# eagle-TSL230RD.net
KiCad netlist of a schematic drawn in EAGLE
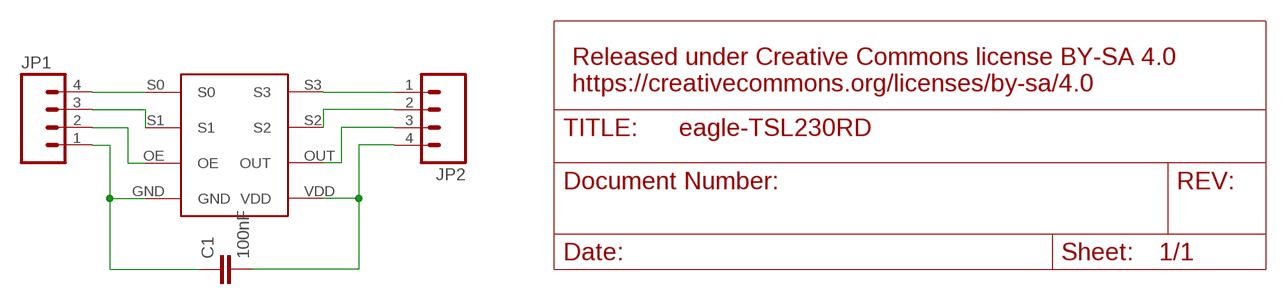
[diagram p0: schematic, sheet 1]

(export (version "E")
  (design (tool "Eeschema 10.0.6"))
  (components
    (comp (ref "C1")
      (value "100nF")
      (footprint "eagle-import:0805")
      (libsource (lib "eagle-import") (part "CAP0805"))
    )
    (comp (ref "JP1")
      (value "M04PTH")
      (footprint "eagle-import:1X04")
      (libsource (lib "eagle-import") (part "M04PTH"))
    )
    (comp (ref "JP2")
      (value "M04PTH")
      (footprint "eagle-import:1X04")
      (libsource (lib "eagle-import") (part "M04PTH"))
    )
    (comp (ref "U$1")
      (value "TSL230RDSMD")
      (footprint "eagle-import:TSL230RD")
      (libsource (lib "eagle-import") (part "TSL230RDSMD"))
    )
  )
  (nets
    (net (code "1") (name "Net-(C1-Pad1)") (class "Default")
      (node (ref "C1") (pin "1") (pinfunction "1_1") (pintype "passive"))
      (node (ref "JP1") (pin "1") (pinfunction "1_1") (pintype "passive"))
      (node (ref "U$1") (pin "GND") (pinfunction "GND_GND") (pintype "bidirectional"))
    )
    (net (code "2") (name "Net-(C1-Pad2)") (class "Default")
      (node (ref "C1") (pin "2") (pinfunction "2_2") (pintype "passive"))
      (node (ref "JP2") (pin "4") (pinfunction "4_4") (pintype "passive"))
      (node (ref "U$1") (pin "VDD") (pinfunction "VDD_VDD") (pintype "bidirectional"))
    )
    (net (code "3") (name "Net-(JP1-Pad2)") (class "Default")
      (node (ref "JP1") (pin "2") (pinfunction "2_2") (pintype "passive"))
      (node (ref "U$1") (pin "OE") (pinfunction "OE_OE") (pintype "bidirectional"))
    )
    (net (code "4") (name "Net-(JP1-Pad3)") (class "Default")
      (node (ref "JP1") (pin "3") (pinfunction "3_3") (pintype "passive"))
      (node (ref "U$1") (pin "S1") (pinfunction "S1_S1") (pintype "bidirectional"))
    )
    (net (code "5") (name "Net-(JP1-Pad4)") (class "Default")
      (node (ref "JP1") (pin "4") (pinfunction "4_4") (pintype "passive"))
      (node (ref "U$1") (pin "S0") (pinfunction "S0_S0") (pintype "bidirectional"))
    )
    (net (code "6") (name "Net-(JP2-Pad1)") (class "Default")
      (node (ref "JP2") (pin "1") (pinfunction "1_1") (pintype "passive"))
      (node (ref "U$1") (pin "S3") (pinfunction "S3_S3") (pintype "bidirectional"))
    )
    (net (code "7") (name "Net-(JP2-Pad2)") (class "Default")
      (node (ref "JP2") (pin "2") (pinfunction "2_2") (pintype "passive"))
      (node (ref "U$1") (pin "S2") (pinfunction "S2_S2") (pintype "bidirectional"))
    )
    (net (code "8") (name "Net-(JP2-Pad3)") (class "Default")
      (node (ref "JP2") (pin "3") (pinfunction "3_3") (pintype "passive"))
      (node (ref "U$1") (pin "OUT") (pinfunction "OUT_OUT") (pintype "bidirectional"))
    )
  )
)
